# SoftCore_SA_P2.net
KiCad netlist of a schematic drawn in Altium Designer
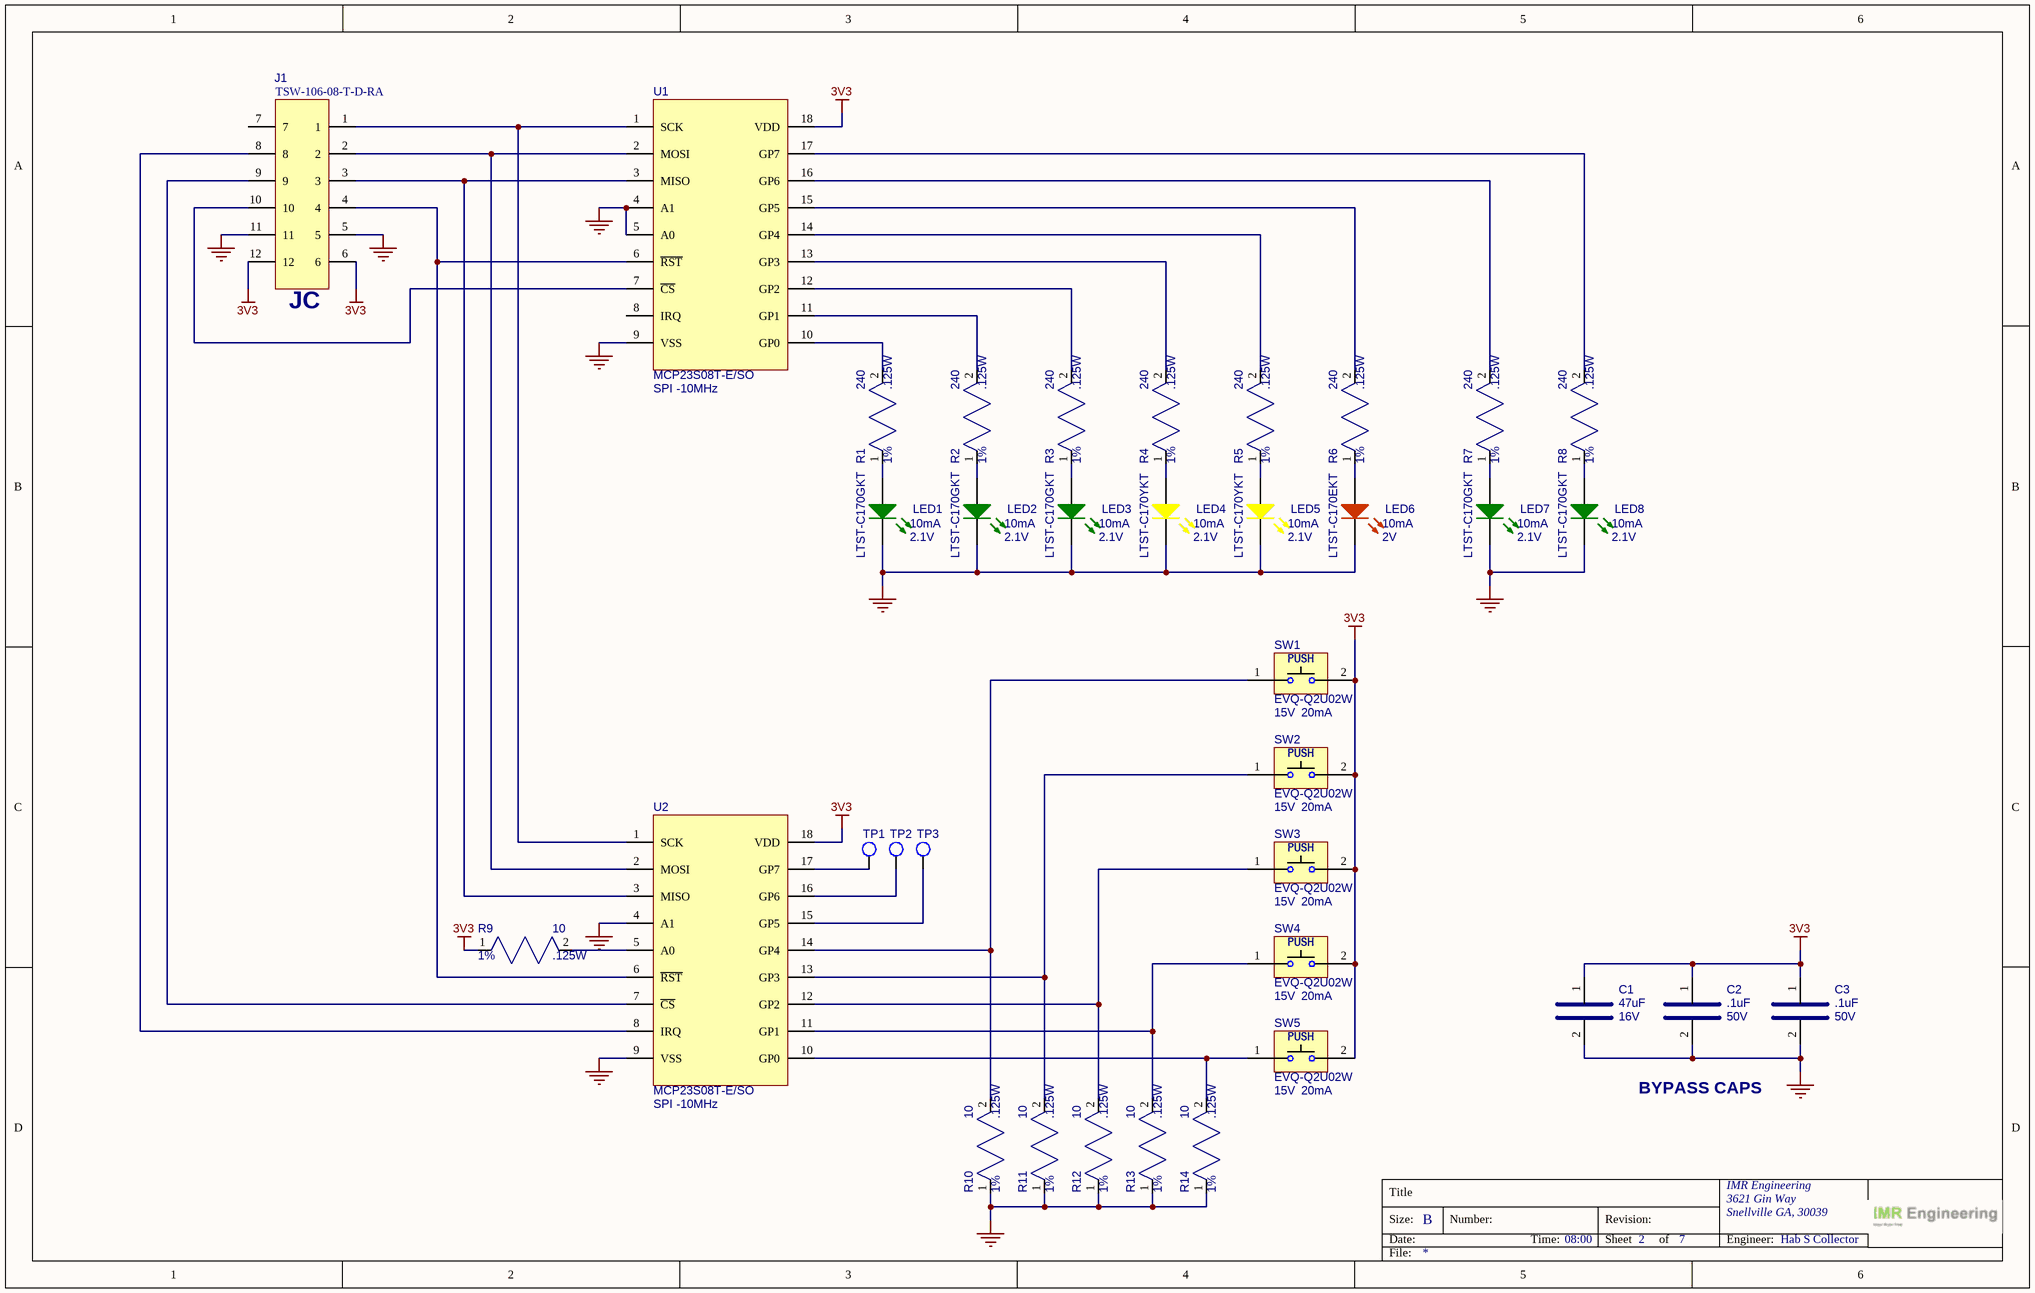
[diagram p0: SoftCore_SA_P2.SchDoc]

(export (version "E")
  (design (tool "Eeschema 10.0.6"))
  (components
    (comp (ref "C1")
      (value "47uF")
      (footprint "CAP_1210")
      (description "CAP CER 47UF 50V X5R 1210")
      (fields
        (field (name "MFG") "Murata Electronics")
        (field (name "VOLTAGE") "16V")
        (field (name "Comment") "GRM32ER60J476ME20L")
      )
      (libsource (lib "IMR_LIB_SCH_R2") (part "CAP_SMD_47UF_16V_1210"))
    )
    (comp (ref "C2")
      (value ".1uF")
      (footprint "CAP_0805")
      (description "CAP CER 0.1UF 50V X7R 0805")
      (fields
        (field (name "MFG") "KYOCERA AVX")
        (field (name "VOLTAGE") "50V")
        (field (name "Comment") "KGM21NR71H104KT")
      )
      (libsource (lib "IMR_LIB_SCH_R2") (part "CAP_SMD_0.1UF_50V_0805"))
    )
    (comp (ref "C3")
      (value ".1uF")
      (footprint "CAP_0805")
      (description "CAP CER 0.1UF 50V X7R 0805")
      (fields
        (field (name "MFG") "KYOCERA AVX")
        (field (name "VOLTAGE") "50V")
        (field (name "Comment") "KGM21NR71H104KT")
      )
      (libsource (lib "IMR_LIB_SCH_R2") (part "CAP_SMD_0.1UF_50V_0805"))
    )
    (comp (ref "J1")
      (value "TSW-106-08-T-D-RA")
      (footprint "SAMTEC_TSW-106-08-T-D-RA")
      (description "CONN HEADER R/A 12POS 2.54MM")
      (fields (field (name "MFG") "Samtec Inc.") (field (name "MFG_PN") "TSW-106-08-T-D-RA"))
      (libsource (lib "IMR_LIB_SCH_R2") (part "CONN_HEADER_12P_100MIL_RA"))
    )
    (comp (ref "LED1")
      (value "2.1V")
      (footprint "LED_0805")
      (description "LED GREEN CLEAR SMD")
      (fields
        (field (name "MFG") "Lite-On")
        (field (name "MFG_PN") "LTST-C170GKT")
        (field (name "CURRENT") "10mA")
        (field (name "Comment") "LTST-C170GKT")
      )
      (libsource (lib "IMR_LIB_SCH_R2") (part "LED_GREEN_LTST-C170GKT"))
    )
    (comp (ref "LED2")
      (value "2.1V")
      (footprint "LED_0805")
      (description "LED GREEN CLEAR SMD")
      (fields
        (field (name "MFG") "Lite-On")
        (field (name "MFG_PN") "LTST-C170GKT")
        (field (name "CURRENT") "10mA")
        (field (name "Comment") "LTST-C170GKT")
      )
      (libsource (lib "IMR_LIB_SCH_R2") (part "LED_GREEN_LTST-C170GKT"))
    )
    (comp (ref "LED3")
      (value "2.1V")
      (footprint "LED_0805")
      (description "LED GREEN CLEAR SMD")
      (fields
        (field (name "MFG") "Lite-On")
        (field (name "MFG_PN") "LTST-C170GKT")
        (field (name "CURRENT") "10mA")
        (field (name "Comment") "LTST-C170GKT")
      )
      (libsource (lib "IMR_LIB_SCH_R2") (part "LED_GREEN_LTST-C170GKT"))
    )
    (comp (ref "LED4")
      (value "2.1V")
      (footprint "LED_0805")
      (description "LED YELLOW CLEAR SMD")
      (fields
        (field (name "MFG") "Lite-On")
        (field (name "MFG_PN") "LTST-C170YKT")
        (field (name "CURRENT") "10mA")
        (field (name "Comment") "LTST-C170YKT")
      )
      (libsource (lib "IMR_LIB_SCH_R2") (part "LED_YELLOW_LTST-C170YKT"))
    )
    (comp (ref "LED5")
      (value "2.1V")
      (footprint "LED_0805")
      (description "LED YELLOW CLEAR SMD")
      (fields
        (field (name "MFG") "Lite-On")
        (field (name "MFG_PN") "LTST-C170YKT")
        (field (name "CURRENT") "10mA")
        (field (name "Comment") "LTST-C170YKT")
      )
      (libsource (lib "IMR_LIB_SCH_R2") (part "LED_YELLOW_LTST-C170YKT"))
    )
    (comp (ref "LED6")
      (value "2V")
      (footprint "LED_0805")
      (description "LED RED CLEAR SMD")
      (fields
        (field (name "MFG") "Lite-On")
        (field (name "MFG_PN") "LTST-C170EKT")
        (field (name "CURRENT") "10mA")
        (field (name "Comment") "LTST-C170EKT")
      )
      (libsource (lib "IMR_LIB_SCH_R2") (part "LED_RED_LTST-C170EKT"))
    )
    (comp (ref "LED7")
      (value "2.1V")
      (footprint "LED_0805")
      (description "LED GREEN CLEAR SMD")
      (fields
        (field (name "MFG") "Lite-On")
        (field (name "MFG_PN") "LTST-C170GKT")
        (field (name "CURRENT") "10mA")
        (field (name "Comment") "LTST-C170GKT")
      )
      (libsource (lib "IMR_LIB_SCH_R2") (part "LED_GREEN_LTST-C170GKT"))
    )
    (comp (ref "LED8")
      (value "2.1V")
      (footprint "LED_0805")
      (description "LED GREEN CLEAR SMD")
      (fields
        (field (name "MFG") "Lite-On")
        (field (name "MFG_PN") "LTST-C170GKT")
        (field (name "CURRENT") "10mA")
        (field (name "Comment") "LTST-C170GKT")
      )
      (libsource (lib "IMR_LIB_SCH_R2") (part "LED_GREEN_LTST-C170GKT"))
    )
    (comp (ref "R1")
      (value "240")
      (footprint "RES_0805")
      (description "RES SMD 240 OHM 1% 1/8W 0805")
      (fields
        (field (name "MFG") "Yageo")
        (field (name "POWER") ".125W")
        (field (name "TOLERANCE") "1%")
        (field (name "Comment") "RC0805FR-13240RL")
      )
      (libsource (lib "IMR_LIB_SCH_R2") (part "RES_SMD_240_0805_1/8W_1%"))
    )
    (comp (ref "R2")
      (value "240")
      (footprint "RES_0805")
      (description "RES SMD 240 OHM 1% 1/8W 0805")
      (fields
        (field (name "MFG") "Yageo")
        (field (name "POWER") ".125W")
        (field (name "TOLERANCE") "1%")
        (field (name "Comment") "RC0805FR-13240RL")
      )
      (libsource (lib "IMR_LIB_SCH_R2") (part "RES_SMD_240_0805_1/8W_1%"))
    )
    (comp (ref "R3")
      (value "240")
      (footprint "RES_0805")
      (description "RES SMD 240 OHM 1% 1/8W 0805")
      (fields
        (field (name "MFG") "Yageo")
        (field (name "POWER") ".125W")
        (field (name "TOLERANCE") "1%")
        (field (name "Comment") "RC0805FR-13240RL")
      )
      (libsource (lib "IMR_LIB_SCH_R2") (part "RES_SMD_240_0805_1/8W_1%"))
    )
    (comp (ref "R4")
      (value "240")
      (footprint "RES_0805")
      (description "RES SMD 240 OHM 1% 1/8W 0805")
      (fields
        (field (name "MFG") "Yageo")
        (field (name "POWER") ".125W")
        (field (name "TOLERANCE") "1%")
        (field (name "Comment") "RC0805FR-13240RL")
      )
      (libsource (lib "IMR_LIB_SCH_R2") (part "RES_SMD_240_0805_1/8W_1%"))
    )
    (comp (ref "R5")
      (value "240")
      (footprint "RES_0805")
      (description "RES SMD 240 OHM 1% 1/8W 0805")
      (fields
        (field (name "MFG") "Yageo")
        (field (name "POWER") ".125W")
        (field (name "TOLERANCE") "1%")
        (field (name "Comment") "RC0805FR-13240RL")
      )
      (libsource (lib "IMR_LIB_SCH_R2") (part "RES_SMD_240_0805_1/8W_1%"))
    )
    (comp (ref "R6")
      (value "240")
      (footprint "RES_0805")
      (description "RES SMD 240 OHM 1% 1/8W 0805")
      (fields
        (field (name "MFG") "Yageo")
        (field (name "POWER") ".125W")
        (field (name "TOLERANCE") "1%")
        (field (name "Comment") "RC0805FR-13240RL")
      )
      (libsource (lib "IMR_LIB_SCH_R2") (part "RES_SMD_240_0805_1/8W_1%"))
    )
    (comp (ref "R7")
      (value "240")
      (footprint "RES_0805")
      (description "RES SMD 240 OHM 1% 1/8W 0805")
      (fields
        (field (name "MFG") "Yageo")
        (field (name "POWER") ".125W")
        (field (name "TOLERANCE") "1%")
        (field (name "Comment") "RC0805FR-13240RL")
      )
      (libsource (lib "IMR_LIB_SCH_R2") (part "RES_SMD_240_0805_1/8W_1%"))
    )
    (comp (ref "R8")
      (value "240")
      (footprint "RES_0805")
      (description "RES SMD 240 OHM 1% 1/8W 0805")
      (fields
        (field (name "MFG") "Yageo")
        (field (name "POWER") ".125W")
        (field (name "TOLERANCE") "1%")
        (field (name "Comment") "RC0805FR-13240RL")
      )
      (libsource (lib "IMR_LIB_SCH_R2") (part "RES_SMD_240_0805_1/8W_1%"))
    )
    (comp (ref "R9")
      (value "10")
      (footprint "RES_0805")
      (description "RES SMD 10 OHM 1% 1/8W 0805")
      (fields
        (field (name "MFG") "Yageo")
        (field (name "POWER") ".125W")
        (field (name "TOLERANCE") "1%")
        (field (name "Comment") "RC0805FR-1310RL")
      )
      (libsource (lib "IMR_LIB_SCH_R2") (part "RES_SMD_10_0805_1/8W_1%"))
    )
    (comp (ref "R10")
      (value "10")
      (footprint "RES_0805")
      (description "RES SMD 10 OHM 1% 1/8W 0805")
      (fields
        (field (name "MFG") "Yageo")
        (field (name "POWER") ".125W")
        (field (name "TOLERANCE") "1%")
        (field (name "Comment") "RC0805FR-1310RL")
      )
      (libsource (lib "IMR_LIB_SCH_R2") (part "RES_SMD_10_0805_1/8W_1%"))
    )
    (comp (ref "R11")
      (value "10")
      (footprint "RES_0805")
      (description "RES SMD 10 OHM 1% 1/8W 0805")
      (fields
        (field (name "MFG") "Yageo")
        (field (name "POWER") ".125W")
        (field (name "TOLERANCE") "1%")
        (field (name "Comment") "RC0805FR-1310RL")
      )
      (libsource (lib "IMR_LIB_SCH_R2") (part "RES_SMD_10_0805_1/8W_1%"))
    )
    (comp (ref "R12")
      (value "10")
      (footprint "RES_0805")
      (description "RES SMD 10 OHM 1% 1/8W 0805")
      (fields
        (field (name "MFG") "Yageo")
        (field (name "POWER") ".125W")
        (field (name "TOLERANCE") "1%")
        (field (name "Comment") "RC0805FR-1310RL")
      )
      (libsource (lib "IMR_LIB_SCH_R2") (part "RES_SMD_10_0805_1/8W_1%"))
    )
    (comp (ref "R13")
      (value "10")
      (footprint "RES_0805")
      (description "RES SMD 10 OHM 1% 1/8W 0805")
      (fields
        (field (name "MFG") "Yageo")
        (field (name "POWER") ".125W")
        (field (name "TOLERANCE") "1%")
        (field (name "Comment") "RC0805FR-1310RL")
      )
      (libsource (lib "IMR_LIB_SCH_R2") (part "RES_SMD_10_0805_1/8W_1%"))
    )
    (comp (ref "R14")
      (value "10")
      (footprint "RES_0805")
      (description "RES SMD 10 OHM 1% 1/8W 0805")
      (fields
        (field (name "MFG") "Yageo")
        (field (name "POWER") ".125W")
        (field (name "TOLERANCE") "1%")
        (field (name "Comment") "RC0805FR-1310RL")
      )
      (libsource (lib "IMR_LIB_SCH_R2") (part "RES_SMD_10_0805_1/8W_1%"))
    )
    (comp (ref "SW1")
      (value "15V")
      (footprint "PANASONIC_EVQ-Q2U02W")
      (description "SWITCH TACTILE SPST-NO 0.02A 15V")
      (fields
        (field (name "MFG") "American Zettler")
        (field (name "MFG_PN") "EVQ-Q2U02W")
        (field (name "CURRENT") "20mA")
        (field (name "Comment") "EVQ-Q2U02W")
      )
      (libsource (lib "IMR_LIB_SCH_R2") (part "SWITCH_EVQ-Q2U02W"))
    )
    (comp (ref "SW2")
      (value "15V")
      (footprint "PANASONIC_EVQ-Q2U02W")
      (description "SWITCH TACTILE SPST-NO 0.02A 15V")
      (fields
        (field (name "MFG") "American Zettler")
        (field (name "MFG_PN") "EVQ-Q2U02W")
        (field (name "CURRENT") "20mA")
        (field (name "Comment") "EVQ-Q2U02W")
      )
      (libsource (lib "IMR_LIB_SCH_R2") (part "SWITCH_EVQ-Q2U02W"))
    )
    (comp (ref "SW3")
      (value "15V")
      (footprint "PANASONIC_EVQ-Q2U02W")
      (description "SWITCH TACTILE SPST-NO 0.02A 15V")
      (fields
        (field (name "MFG") "American Zettler")
        (field (name "MFG_PN") "EVQ-Q2U02W")
        (field (name "CURRENT") "20mA")
        (field (name "Comment") "EVQ-Q2U02W")
      )
      (libsource (lib "IMR_LIB_SCH_R2") (part "SWITCH_EVQ-Q2U02W"))
    )
    (comp (ref "SW4")
      (value "15V")
      (footprint "PANASONIC_EVQ-Q2U02W")
      (description "SWITCH TACTILE SPST-NO 0.02A 15V")
      (fields
        (field (name "MFG") "American Zettler")
        (field (name "MFG_PN") "EVQ-Q2U02W")
        (field (name "CURRENT") "20mA")
        (field (name "Comment") "EVQ-Q2U02W")
      )
      (libsource (lib "IMR_LIB_SCH_R2") (part "SWITCH_EVQ-Q2U02W"))
    )
    (comp (ref "SW5")
      (value "15V")
      (footprint "PANASONIC_EVQ-Q2U02W")
      (description "SWITCH TACTILE SPST-NO 0.02A 15V")
      (fields
        (field (name "MFG") "American Zettler")
        (field (name "MFG_PN") "EVQ-Q2U02W")
        (field (name "CURRENT") "20mA")
        (field (name "Comment") "EVQ-Q2U02W")
      )
      (libsource (lib "IMR_LIB_SCH_R2") (part "SWITCH_EVQ-Q2U02W"))
    )
    (comp (ref "TP1")
      (value "~")
      (footprint "TEST_POINT_20MIL_TH")
      (description "TEST POINT TH 20MIL HOLE")
      (libsource (lib "IMR_LIB_SCH_R2") (part "CONN_TEST_POINT_TH_PAD_20MIL"))
    )
    (comp (ref "TP2")
      (value "~")
      (footprint "TEST_POINT_20MIL_TH")
      (description "TEST POINT TH 20MIL HOLE")
      (libsource (lib "IMR_LIB_SCH_R2") (part "CONN_TEST_POINT_TH_PAD_20MIL"))
    )
    (comp (ref "TP3")
      (value "~")
      (footprint "TEST_POINT_20MIL_TH")
      (description "TEST POINT TH 20MIL HOLE")
      (libsource (lib "IMR_LIB_SCH_R2") (part "CONN_TEST_POINT_TH_PAD_20MIL"))
    )
    (comp (ref "U1")
      (value "SPI -10MHz")
      (footprint "SOIC-18_300")
      (description "IC IO XPNDR 10MHZ SPI 18SOIC")
      (fields
        (field (name "MFG") "Microchip")
        (field (name "MFG_PN") "MCP23S08T-E/SO")
        (field (name "Comment") "MCP23S08T-E/SO")
      )
      (libsource (lib "IMR_LIB_SCH_R2") (part "IC_MCP23S08T-E/SO"))
    )
    (comp (ref "U2")
      (value "SPI -10MHz")
      (footprint "SOIC-18_300")
      (description "IC IO XPNDR 10MHZ SPI 18SOIC")
      (fields
        (field (name "MFG") "Microchip")
        (field (name "MFG_PN") "MCP23S08T-E/SO")
        (field (name "Comment") "MCP23S08T-E/SO")
      )
      (libsource (lib "IMR_LIB_SCH_R2") (part "IC_MCP23S08T-E/SO"))
    )
  )
  (nets
    (net (code "1") (name "3V3") (class "Default")
      (node (ref "C1") (pin "1") (pinfunction "1_1") (pintype "passive"))
      (node (ref "C2") (pin "1") (pinfunction "1_1") (pintype "passive"))
      (node (ref "C3") (pin "1") (pinfunction "1_1") (pintype "passive"))
      (node (ref "J1") (pin "12") (pinfunction "12_12") (pintype "passive"))
      (node (ref "J1") (pin "6") (pinfunction "6_6") (pintype "passive"))
      (node (ref "R9") (pin "1") (pinfunction "1_1") (pintype "passive"))
      (node (ref "SW1") (pin "2") (pinfunction "B'_2") (pintype "passive"))
      (node (ref "SW2") (pin "2") (pinfunction "B'_2") (pintype "passive"))
      (node (ref "SW3") (pin "2") (pinfunction "B'_2") (pintype "passive"))
      (node (ref "SW4") (pin "2") (pinfunction "B'_2") (pintype "passive"))
      (node (ref "SW5") (pin "2") (pinfunction "B'_2") (pintype "passive"))
      (node (ref "U1") (pin "18") (pinfunction "VDD_18") (pintype "passive"))
      (node (ref "U2") (pin "18") (pinfunction "VDD_18") (pintype "passive"))
    )
    (net (code "2") (name "GND") (class "Default")
      (node (ref "C1") (pin "2") (pinfunction "2_2") (pintype "passive"))
      (node (ref "C2") (pin "2") (pinfunction "2_2") (pintype "passive"))
      (node (ref "C3") (pin "2") (pinfunction "2_2") (pintype "passive"))
      (node (ref "J1") (pin "11") (pinfunction "11_11") (pintype "passive"))
      (node (ref "J1") (pin "5") (pinfunction "5_5") (pintype "passive"))
      (node (ref "LED1") (pin "K") (pinfunction "K_K") (pintype "passive"))
      (node (ref "LED2") (pin "K") (pinfunction "K_K") (pintype "passive"))
      (node (ref "LED3") (pin "K") (pinfunction "K_K") (pintype "passive"))
      (node (ref "LED4") (pin "K") (pinfunction "K_K") (pintype "passive"))
      (node (ref "LED5") (pin "K") (pinfunction "K_K") (pintype "passive"))
      (node (ref "LED6") (pin "K") (pinfunction "K_K") (pintype "passive"))
      (node (ref "LED7") (pin "K") (pinfunction "K_K") (pintype "passive"))
      (node (ref "LED8") (pin "K") (pinfunction "K_K") (pintype "passive"))
      (node (ref "R10") (pin "1") (pinfunction "1_1") (pintype "passive"))
      (node (ref "R11") (pin "1") (pinfunction "1_1") (pintype "passive"))
      (node (ref "R12") (pin "1") (pinfunction "1_1") (pintype "passive"))
      (node (ref "R13") (pin "1") (pinfunction "1_1") (pintype "passive"))
      (node (ref "R14") (pin "1") (pinfunction "1_1") (pintype "passive"))
      (node (ref "U1") (pin "4") (pinfunction "A1_4") (pintype "passive"))
      (node (ref "U1") (pin "5") (pinfunction "A0_5") (pintype "passive"))
      (node (ref "U1") (pin "9") (pinfunction "VSS_9") (pintype "passive"))
      (node (ref "U2") (pin "4") (pinfunction "A1_4") (pintype "passive"))
      (node (ref "U2") (pin "9") (pinfunction "VSS_9") (pintype "passive"))
    )
    (net (code "3") (name "Net-(LED1-PadA)") (class "Default")
      (node (ref "LED1") (pin "A") (pinfunction "A_A") (pintype "passive"))
      (node (ref "R1") (pin "1") (pinfunction "1_1") (pintype "passive"))
    )
    (net (code "4") (name "Net-(LED2-PadA)") (class "Default")
      (node (ref "LED2") (pin "A") (pinfunction "A_A") (pintype "passive"))
      (node (ref "R2") (pin "1") (pinfunction "1_1") (pintype "passive"))
    )
    (net (code "5") (name "Net-(LED3-PadA)") (class "Default")
      (node (ref "LED3") (pin "A") (pinfunction "A_A") (pintype "passive"))
      (node (ref "R3") (pin "1") (pinfunction "1_1") (pintype "passive"))
    )
    (net (code "6") (name "Net-(LED4-PadA)") (class "Default")
      (node (ref "LED4") (pin "A") (pinfunction "A_A") (pintype "passive"))
      (node (ref "R4") (pin "1") (pinfunction "1_1") (pintype "passive"))
    )
    (net (code "7") (name "Net-(LED5-PadA)") (class "Default")
      (node (ref "LED5") (pin "A") (pinfunction "A_A") (pintype "passive"))
      (node (ref "R5") (pin "1") (pinfunction "1_1") (pintype "passive"))
    )
    (net (code "8") (name "Net-(LED6-PadA)") (class "Default")
      (node (ref "LED6") (pin "A") (pinfunction "A_A") (pintype "passive"))
      (node (ref "R6") (pin "1") (pinfunction "1_1") (pintype "passive"))
    )
    (net (code "9") (name "Net-(LED7-PadA)") (class "Default")
      (node (ref "LED7") (pin "A") (pinfunction "A_A") (pintype "passive"))
      (node (ref "R7") (pin "1") (pinfunction "1_1") (pintype "passive"))
    )
    (net (code "10") (name "Net-(LED8-PadA)") (class "Default")
      (node (ref "LED8") (pin "A") (pinfunction "A_A") (pintype "passive"))
      (node (ref "R8") (pin "1") (pinfunction "1_1") (pintype "passive"))
    )
    (net (code "11") (name "Net-(SW1-B)") (class "Default")
      (node (ref "R10") (pin "2") (pinfunction "2_2") (pintype "passive"))
      (node (ref "SW1") (pin "1") (pinfunction "B_1") (pintype "passive"))
      (node (ref "U2") (pin "14") (pinfunction "GP4_14") (pintype "passive"))
    )
    (net (code "12") (name "Net-(SW2-B)") (class "Default")
      (node (ref "R11") (pin "2") (pinfunction "2_2") (pintype "passive"))
      (node (ref "SW2") (pin "1") (pinfunction "B_1") (pintype "passive"))
      (node (ref "U2") (pin "13") (pinfunction "GP3_13") (pintype "passive"))
    )
    (net (code "13") (name "Net-(SW3-B)") (class "Default")
      (node (ref "R12") (pin "2") (pinfunction "2_2") (pintype "passive"))
      (node (ref "SW3") (pin "1") (pinfunction "B_1") (pintype "passive"))
      (node (ref "U2") (pin "12") (pinfunction "GP2_12") (pintype "passive"))
    )
    (net (code "14") (name "Net-(SW4-B)") (class "Default")
      (node (ref "R13") (pin "2") (pinfunction "2_2") (pintype "passive"))
      (node (ref "SW4") (pin "1") (pinfunction "B_1") (pintype "passive"))
      (node (ref "U2") (pin "11") (pinfunction "GP1_11") (pintype "passive"))
    )
    (net (code "15") (name "Net-(SW5-B)") (class "Default")
      (node (ref "R14") (pin "2") (pinfunction "2_2") (pintype "passive"))
      (node (ref "SW5") (pin "1") (pinfunction "B_1") (pintype "passive"))
      (node (ref "U2") (pin "10") (pinfunction "GP0_10") (pintype "passive"))
    )
    (net (code "16") (name "Net-(U1-GP0)") (class "Default")
      (node (ref "R1") (pin "2") (pinfunction "2_2") (pintype "passive"))
      (node (ref "U1") (pin "10") (pinfunction "GP0_10") (pintype "passive"))
    )
    (net (code "17") (name "Net-(U1-GP1)") (class "Default")
      (node (ref "R2") (pin "2") (pinfunction "2_2") (pintype "passive"))
      (node (ref "U1") (pin "11") (pinfunction "GP1_11") (pintype "passive"))
    )
    (net (code "18") (name "Net-(U1-GP2)") (class "Default")
      (node (ref "R3") (pin "2") (pinfunction "2_2") (pintype "passive"))
      (node (ref "U1") (pin "12") (pinfunction "GP2_12") (pintype "passive"))
    )
    (net (code "19") (name "Net-(U1-GP3)") (class "Default")
      (node (ref "R4") (pin "2") (pinfunction "2_2") (pintype "passive"))
      (node (ref "U1") (pin "13") (pinfunction "GP3_13") (pintype "passive"))
    )
    (net (code "20") (name "Net-(U1-GP4)") (class "Default")
      (node (ref "R5") (pin "2") (pinfunction "2_2") (pintype "passive"))
      (node (ref "U1") (pin "14") (pinfunction "GP4_14") (pintype "passive"))
    )
    (net (code "21") (name "Net-(U1-GP5)") (class "Default")
      (node (ref "R6") (pin "2") (pinfunction "2_2") (pintype "passive"))
      (node (ref "U1") (pin "15") (pinfunction "GP5_15") (pintype "passive"))
    )
    (net (code "22") (name "Net-(U1-GP6)") (class "Default")
      (node (ref "R7") (pin "2") (pinfunction "2_2") (pintype "passive"))
      (node (ref "U1") (pin "16") (pinfunction "GP6_16") (pintype "passive"))
    )
    (net (code "23") (name "Net-(U1-GP7)") (class "Default")
      (node (ref "R8") (pin "2") (pinfunction "2_2") (pintype "passive"))
      (node (ref "U1") (pin "17") (pinfunction "GP7_17") (pintype "passive"))
    )
    (net (code "24") (name "Net-(U1-MISO)") (class "Default")
      (node (ref "J1") (pin "3") (pinfunction "3_3") (pintype "passive"))
      (node (ref "U1") (pin "3") (pinfunction "MISO_3") (pintype "passive"))
      (node (ref "U2") (pin "3") (pinfunction "MISO_3") (pintype "passive"))
    )
    (net (code "25") (name "Net-(U1-MOSI)") (class "Default")
      (node (ref "J1") (pin "2") (pinfunction "2_2") (pintype "passive"))
      (node (ref "U1") (pin "2") (pinfunction "MOSI_2") (pintype "passive"))
      (node (ref "U2") (pin "2") (pinfunction "MOSI_2") (pintype "passive"))
    )
    (net (code "26") (name "Net-(U1-SCK)") (class "Default")
      (node (ref "J1") (pin "1") (pinfunction "1_1") (pintype "passive"))
      (node (ref "U1") (pin "1") (pinfunction "SCK_1") (pintype "passive"))
      (node (ref "U2") (pin "1") (pinfunction "SCK_1") (pintype "passive"))
    )
    (net (code "27") (name "Net-(U1-~{CS})") (class "Default")
      (node (ref "J1") (pin "10") (pinfunction "10_10") (pintype "passive"))
      (node (ref "U1") (pin "7") (pinfunction "~{CS}_7") (pintype "passive"))
    )
    (net (code "28") (name "Net-(U1-~{RST})") (class "Default")
      (node (ref "J1") (pin "4") (pinfunction "4_4") (pintype "passive"))
      (node (ref "U1") (pin "6") (pinfunction "~{RST}_6") (pintype "passive"))
      (node (ref "U2") (pin "6") (pinfunction "~{RST}_6") (pintype "passive"))
    )
    (net (code "29") (name "Net-(U2-A0)") (class "Default")
      (node (ref "R9") (pin "2") (pinfunction "2_2") (pintype "passive"))
      (node (ref "U2") (pin "5") (pinfunction "A0_5") (pintype "passive"))
    )
    (net (code "30") (name "Net-(U2-GP5)") (class "Default")
      (node (ref "TP3") (pin "1") (pintype "passive"))
      (node (ref "U2") (pin "15") (pinfunction "GP5_15") (pintype "passive"))
    )
    (net (code "31") (name "Net-(U2-GP6)") (class "Default")
      (node (ref "TP2") (pin "1") (pintype "passive"))
      (node (ref "U2") (pin "16") (pinfunction "GP6_16") (pintype "passive"))
    )
    (net (code "32") (name "Net-(U2-GP7)") (class "Default")
      (node (ref "TP1") (pin "1") (pintype "passive"))
      (node (ref "U2") (pin "17") (pinfunction "GP7_17") (pintype "passive"))
    )
    (net (code "33") (name "Net-(U2-IRQ)") (class "Default")
      (node (ref "J1") (pin "8") (pinfunction "8_8") (pintype "passive"))
      (node (ref "U2") (pin "8") (pinfunction "IRQ_8") (pintype "passive"))
    )
    (net (code "34") (name "Net-(U2-~{CS})") (class "Default")
      (node (ref "J1") (pin "9") (pinfunction "9_9") (pintype "passive"))
      (node (ref "U2") (pin "7") (pinfunction "~{CS}_7") (pintype "passive"))
    )
    (net (code "35") (name "unconnected-(J1-Pad7)") (class "Default")
      (node (ref "J1") (pin "7") (pinfunction "7_7") (pintype "passive"))
    )
    (net (code "36") (name "unconnected-(U1-IRQ-Pad8)") (class "Default")
      (node (ref "U1") (pin "8") (pinfunction "IRQ_8") (pintype "passive"))
    )
  )
)
